# DebugCAN.net
KiCad netlist of a schematic drawn in EAGLE
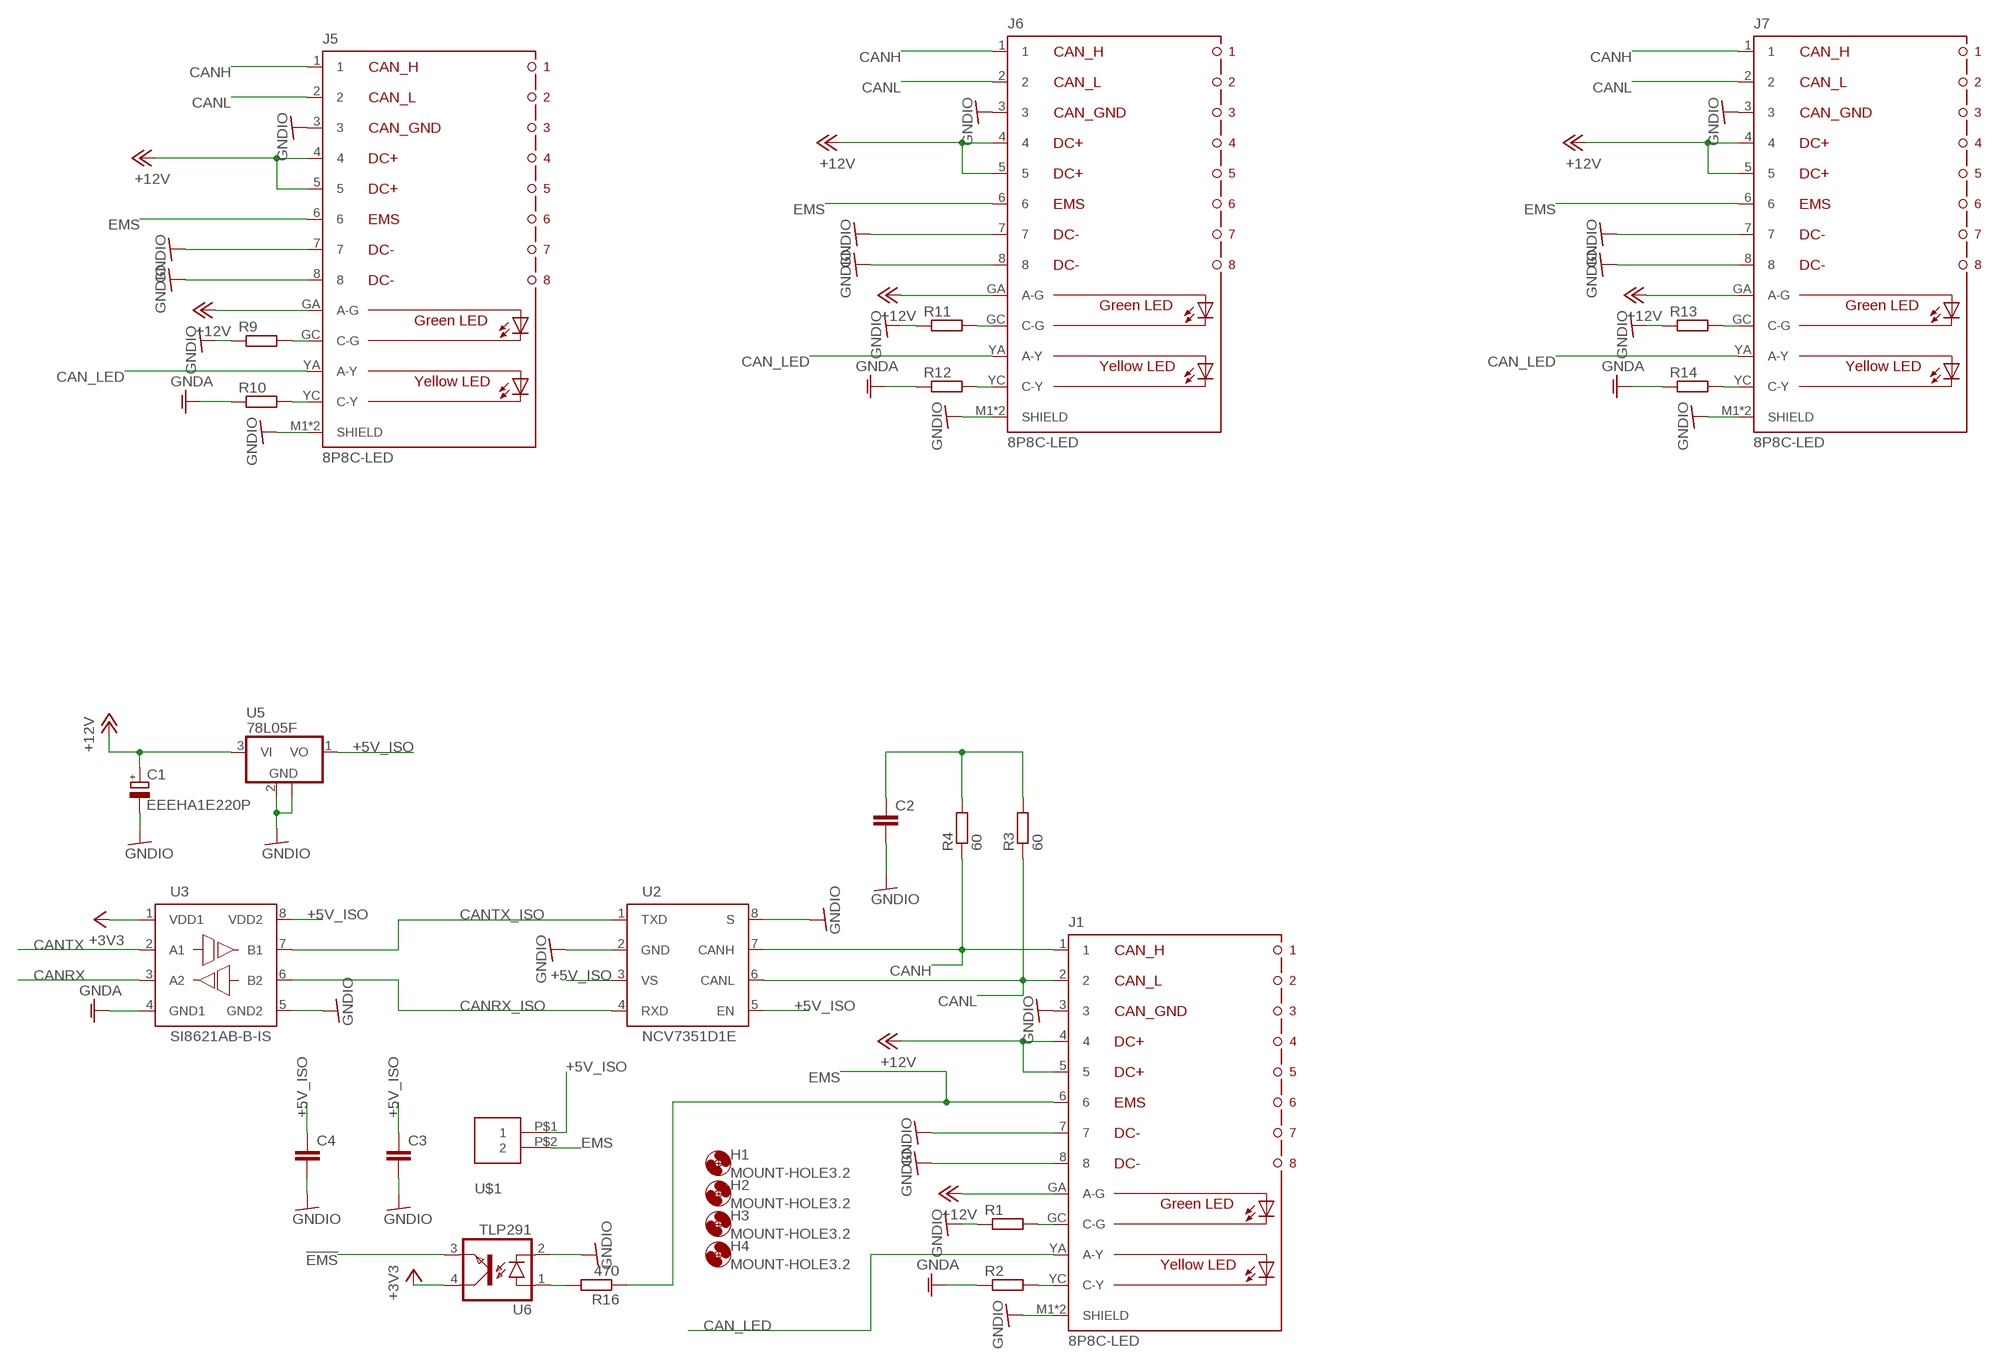
[diagram p0: schematic, sheet 1]
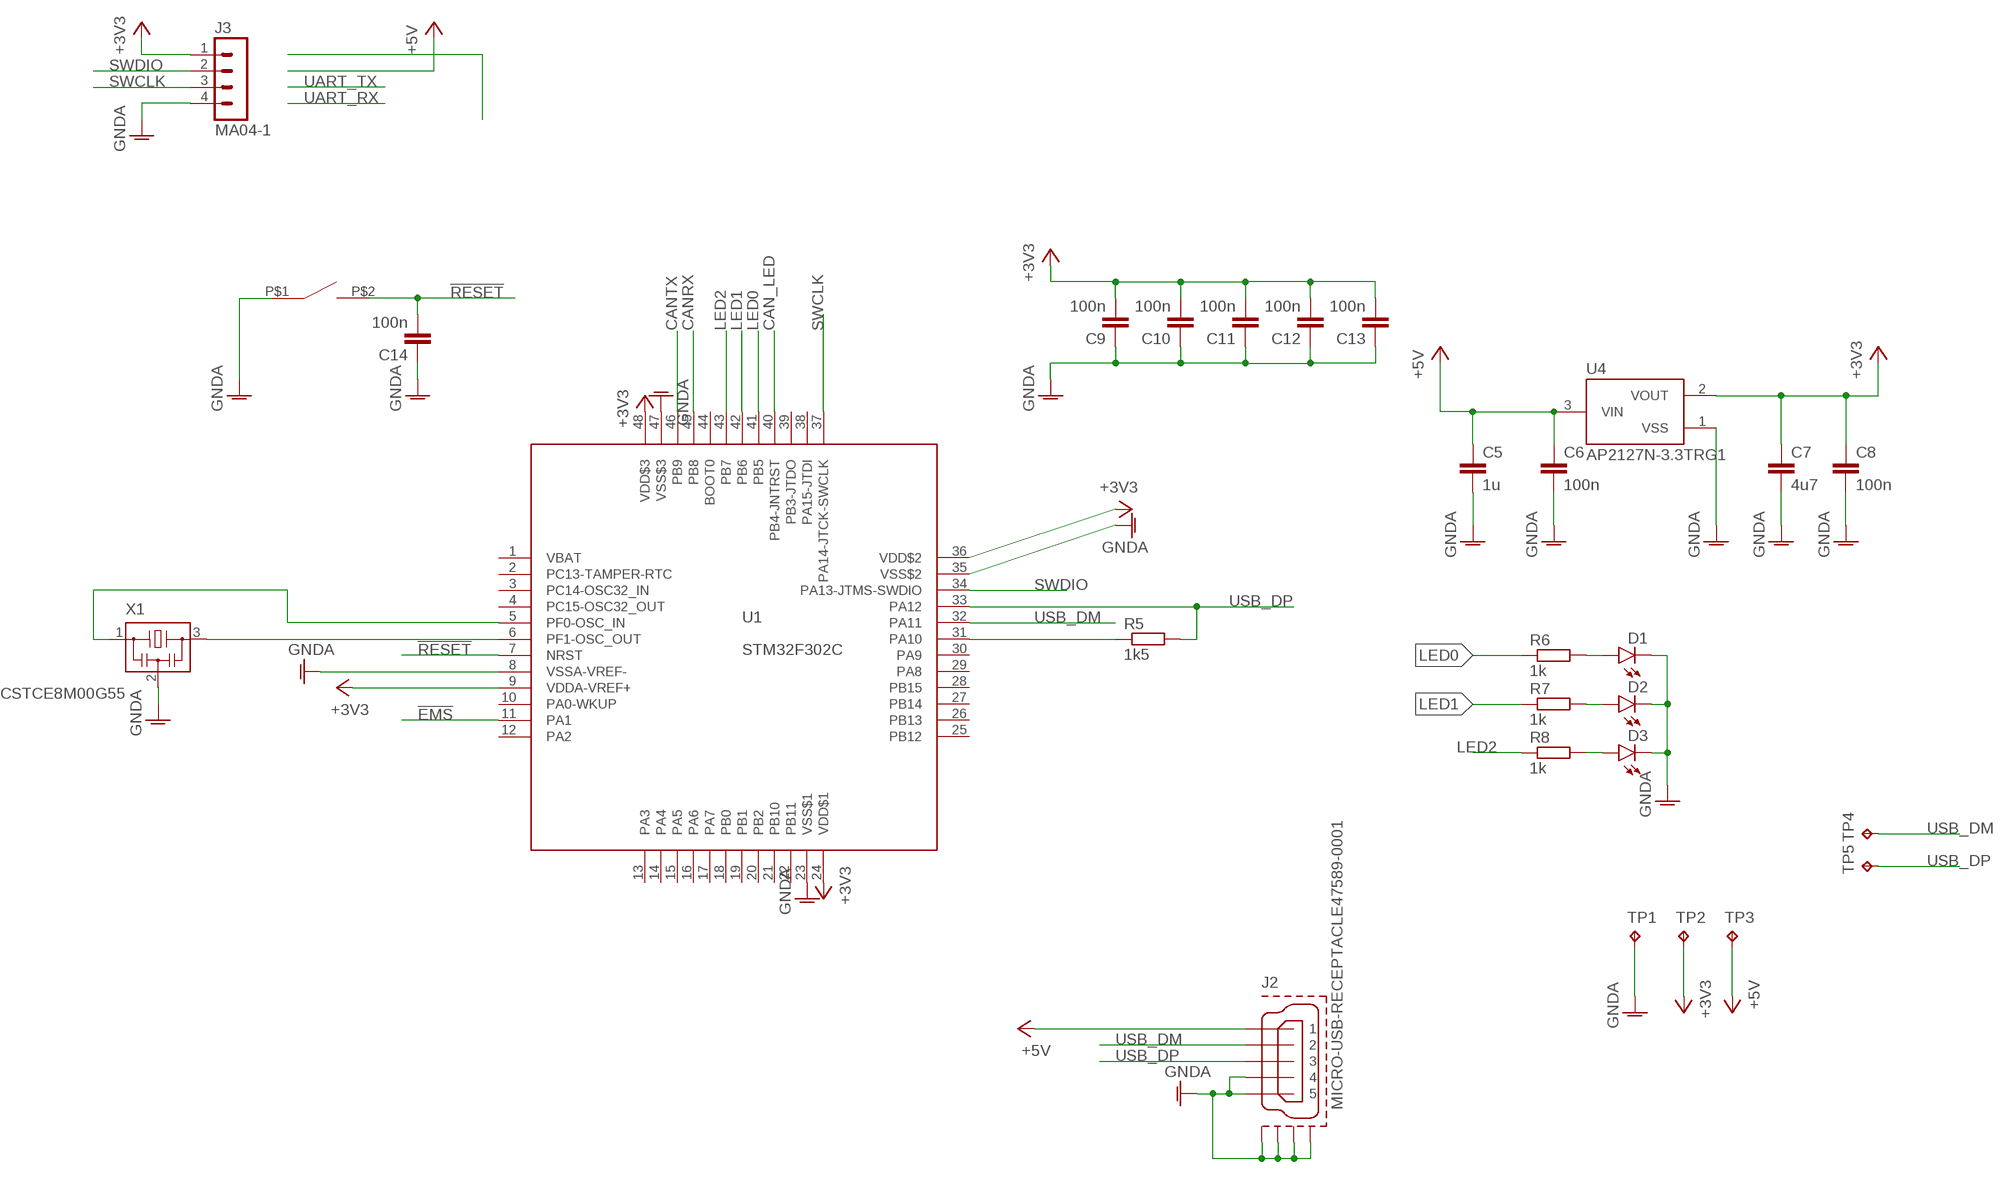
[diagram p1: schematic, sheet 2]

(export (version "E")
  (design (tool "Eeschema 10.0.6"))
  (components
    (comp (ref "C5")
      (value "1u")
      (footprint "eagle-import:C0603")
      (libsource (lib "eagle-import") (part "C-EUC0603"))
    )
    (comp (ref "C6")
      (value "100n")
      (footprint "eagle-import:C0603")
      (libsource (lib "eagle-import") (part "C-EUC0603"))
    )
    (comp (ref "C7")
      (value "4u7")
      (footprint "eagle-import:C0805")
      (libsource (lib "eagle-import") (part "C-EUC0805"))
    )
    (comp (ref "C8")
      (value "100n")
      (footprint "eagle-import:C0603")
      (libsource (lib "eagle-import") (part "C-EUC0603"))
    )
    (comp (ref "C9")
      (value "100n")
      (footprint "eagle-import:C0603")
      (libsource (lib "eagle-import") (part "C-EUC0603"))
    )
    (comp (ref "C10")
      (value "100n")
      (footprint "eagle-import:C0603")
      (libsource (lib "eagle-import") (part "C-EUC0603"))
    )
    (comp (ref "C11")
      (value "100n")
      (footprint "eagle-import:C0603")
      (libsource (lib "eagle-import") (part "C-EUC0603"))
    )
    (comp (ref "C12")
      (value "100n")
      (footprint "eagle-import:C0603")
      (libsource (lib "eagle-import") (part "C-EUC0603"))
    )
    (comp (ref "C13")
      (value "100n")
      (footprint "eagle-import:C0603")
      (libsource (lib "eagle-import") (part "C-EUC0603"))
    )
    (comp (ref "C14")
      (value "100n")
      (footprint "eagle-import:C0603")
      (libsource (lib "eagle-import") (part "C-EUC0603"))
    )
    (comp (ref "D1")
      (value "LEDCHIPLED_0805")
      (footprint "eagle-import:CHIPLED_0805")
      (libsource (lib "eagle-import") (part "LEDCHIPLED_0805"))
    )
    (comp (ref "D2")
      (value "LEDCHIPLED_0805")
      (footprint "eagle-import:CHIPLED_0805")
      (libsource (lib "eagle-import") (part "LEDCHIPLED_0805"))
    )
    (comp (ref "D3")
      (value "LEDCHIPLED_0805")
      (footprint "eagle-import:CHIPLED_0805")
      (libsource (lib "eagle-import") (part "LEDCHIPLED_0805"))
    )
    (comp (ref "J2")
      (value "MICRO-USB-RECEPTACLE47589-0001")
      (footprint "eagle-import:47589-0001")
      (libsource (lib "eagle-import") (part "MICRO-USB-RECEPTACLE47589-0001"))
    )
    (comp (ref "J3")
      (value "MA04-1")
      (footprint "eagle-import:MA04-1")
      (libsource (lib "eagle-import") (part "MA04-1"))
    )
    (comp (ref "R5")
      (value "1k5")
      (footprint "eagle-import:R0603")
      (libsource (lib "eagle-import") (part "R-EU_R0603"))
    )
    (comp (ref "R6")
      (value "1k")
      (footprint "eagle-import:R0603")
      (libsource (lib "eagle-import") (part "R-EU_R0603"))
    )
    (comp (ref "R7")
      (value "1k")
      (footprint "eagle-import:R0603")
      (libsource (lib "eagle-import") (part "R-EU_R0603"))
    )
    (comp (ref "R8")
      (value "1k")
      (footprint "eagle-import:R0603")
      (libsource (lib "eagle-import") (part "R-EU_R0603"))
    )
    (comp (ref "S1")
      (value "SWITCH_TACTILETOP")
      (footprint "eagle-import:SWITCH_TACTILE_3X6")
      (libsource (lib "eagle-import") (part "SWITCH_TACTILETOP"))
    )
    (comp (ref "TP1")
      (value "TPB1,27")
      (footprint "eagle-import:B1,27")
      (libsource (lib "eagle-import") (part "TPB1,27"))
    )
    (comp (ref "TP2")
      (value "TPB1,27")
      (footprint "eagle-import:B1,27")
      (libsource (lib "eagle-import") (part "TPB1,27"))
    )
    (comp (ref "TP3")
      (value "TPB1,27")
      (footprint "eagle-import:B1,27")
      (libsource (lib "eagle-import") (part "TPB1,27"))
    )
    (comp (ref "TP4")
      (value "TPB1,27")
      (footprint "eagle-import:B1,27")
      (libsource (lib "eagle-import") (part "TPB1,27"))
    )
    (comp (ref "TP5")
      (value "TPB1,27")
      (footprint "eagle-import:B1,27")
      (libsource (lib "eagle-import") (part "TPB1,27"))
    )
    (comp (ref "U1")
      (value "STM32F302C")
      (footprint "eagle-import:LQFP48")
      (libsource (lib "eagle-import") (part "STM32F303C"))
    )
    (comp (ref "U4")
      (value "AP2127N-3.3TRG1")
      (footprint "eagle-import:SOT95P240X110-3")
      (libsource (lib "eagle-import") (part "XC6206"))
    )
    (comp (ref "X1")
      (value "CSTCE8M00G55")
      (footprint "eagle-import:CSTCE8M00G55")
      (libsource (lib "eagle-import") (part "CSTCE8M00G55"))
    )
    (comp (ref "C1")
      (value "EEEHA1E220P")
      (footprint "eagle-import:153CLV-0605")
      (libsource (lib "eagle-import") (part "CPOL-EU153CLV-0605"))
    )
    (comp (ref "C2")
      (value "C-EUC0603")
      (footprint "eagle-import:C0603")
      (libsource (lib "eagle-import") (part "rcl_334_C-EUC0603"))
    )
    (comp (ref "C3")
      (value "C-EUC0603")
      (footprint "eagle-import:C0603")
      (libsource (lib "eagle-import") (part "rcl_334_C-EUC0603"))
    )
    (comp (ref "C4")
      (value "C-EUC0603")
      (footprint "eagle-import:C0603")
      (libsource (lib "eagle-import") (part "rcl_334_C-EUC0603"))
    )
    (comp (ref "H1")
      (value "MOUNT-HOLE3.2")
      (footprint "eagle-import:3,2")
      (libsource (lib "eagle-import") (part "MOUNT-HOLE3.2"))
    )
    (comp (ref "H2")
      (value "MOUNT-HOLE3.2")
      (footprint "eagle-import:3,2")
      (libsource (lib "eagle-import") (part "MOUNT-HOLE3.2"))
    )
    (comp (ref "H3")
      (value "MOUNT-HOLE3.2")
      (footprint "eagle-import:3,2")
      (libsource (lib "eagle-import") (part "MOUNT-HOLE3.2"))
    )
    (comp (ref "H4")
      (value "MOUNT-HOLE3.2")
      (footprint "eagle-import:3,2")
      (libsource (lib "eagle-import") (part "MOUNT-HOLE3.2"))
    )
    (comp (ref "J1")
      (value "8P8C-LED")
      (footprint "eagle-import:8P8C-LED")
      (libsource (lib "eagle-import") (part "8P8C-LED"))
    )
    (comp (ref "J5")
      (value "8P8C-LED")
      (footprint "eagle-import:8P8C-LED")
      (libsource (lib "eagle-import") (part "8P8C-LED"))
    )
    (comp (ref "J6")
      (value "8P8C-LED")
      (footprint "eagle-import:8P8C-LED")
      (libsource (lib "eagle-import") (part "8P8C-LED"))
    )
    (comp (ref "J7")
      (value "8P8C-LED")
      (footprint "eagle-import:8P8C-LED")
      (libsource (lib "eagle-import") (part "8P8C-LED"))
    )
    (comp (ref "R1")
      (value "R-EU_R0603")
      (footprint "eagle-import:R0603")
      (libsource (lib "eagle-import") (part "rcl_334_R-EU_R0603"))
    )
    (comp (ref "R2")
      (value "R-EU_R0603")
      (footprint "eagle-import:R0603")
      (libsource (lib "eagle-import") (part "rcl_334_R-EU_R0603"))
    )
    (comp (ref "R3")
      (value "60")
      (footprint "eagle-import:R0603")
      (libsource (lib "eagle-import") (part "rcl_334_R-EU_R0603"))
    )
    (comp (ref "R4")
      (value "60")
      (footprint "eagle-import:R0603")
      (libsource (lib "eagle-import") (part "rcl_334_R-EU_R0603"))
    )
    (comp (ref "R9")
      (value "R-EU_R0603")
      (footprint "eagle-import:R0603")
      (libsource (lib "eagle-import") (part "rcl_334_R-EU_R0603"))
    )
    (comp (ref "R10")
      (value "R-EU_R0603")
      (footprint "eagle-import:R0603")
      (libsource (lib "eagle-import") (part "rcl_334_R-EU_R0603"))
    )
    (comp (ref "R11")
      (value "R-EU_R0603")
      (footprint "eagle-import:R0603")
      (libsource (lib "eagle-import") (part "rcl_334_R-EU_R0603"))
    )
    (comp (ref "R12")
      (value "R-EU_R0603")
      (footprint "eagle-import:R0603")
      (libsource (lib "eagle-import") (part "rcl_334_R-EU_R0603"))
    )
    (comp (ref "R13")
      (value "R-EU_R0603")
      (footprint "eagle-import:R0603")
      (libsource (lib "eagle-import") (part "rcl_334_R-EU_R0603"))
    )
    (comp (ref "R14")
      (value "R-EU_R0603")
      (footprint "eagle-import:R0603")
      (libsource (lib "eagle-import") (part "rcl_334_R-EU_R0603"))
    )
    (comp (ref "R16")
      (value "470")
      (footprint "eagle-import:R0603")
      (libsource (lib "eagle-import") (part "rcl_334_R-EU_R0603"))
    )
    (comp (ref "U$1")
      (value "XH-2-STRAIGHT")
      (footprint "eagle-import:CON-XH-2-STRAIGHT")
      (libsource (lib "eagle-import") (part "XH-2-STRAIGHT"))
    )
    (comp (ref "U2")
      (value "NCV7351D1E")
      (footprint "eagle-import:SO08")
      (libsource (lib "eagle-import") (part "NCV7351D1E"))
    )
    (comp (ref "U3")
      (value "SI8621AB-B-IS")
      (footprint "eagle-import:SO08")
      (libsource (lib "eagle-import") (part "SI8621AB-B-IS"))
    )
    (comp (ref "U5")
      (value "78L05F")
      (footprint "eagle-import:SOT89")
      (libsource (lib "eagle-import") (part "78LF05"))
    )
    (comp (ref "U6")
      (value "TLP291")
      (footprint "eagle-import:MINI-FLAT-4")
      (libsource (lib "eagle-import") (part "TLP291"))
    )
  )
  (nets
    (net (code "1") (name "+3V3") (class "Default")
      (node (ref "C10") (pin "2") (pinfunction "2_2") (pintype "passive"))
      (node (ref "C11") (pin "2") (pinfunction "2_2") (pintype "passive"))
      (node (ref "C12") (pin "2") (pinfunction "2_2") (pintype "passive"))
      (node (ref "C13") (pin "2") (pinfunction "2_2") (pintype "passive"))
      (node (ref "C7") (pin "1") (pinfunction "1_1") (pintype "passive"))
      (node (ref "C8") (pin "1") (pinfunction "1_1") (pintype "passive"))
      (node (ref "C9") (pin "2") (pinfunction "2_2") (pintype "passive"))
      (node (ref "J3") (pin "1") (pinfunction "1_1") (pintype "passive"))
      (node (ref "TP2") (pin "TP") (pinfunction "TP_TP") (pintype "input"))
      (node (ref "U1") (pin "24") (pinfunction "VDD$1_24") (pintype "passive"))
      (node (ref "U1") (pin "36") (pinfunction "VDD$2_36") (pintype "passive"))
      (node (ref "U1") (pin "48") (pinfunction "VDD$3_48") (pintype "passive"))
      (node (ref "U1") (pin "9") (pinfunction "VDDA-VREF+_9") (pintype "bidirectional"))
      (node (ref "U3") (pin "1") (pinfunction "VDD1_1") (pintype "power_in"))
      (node (ref "U4") (pin "2") (pinfunction "VOUT_2") (pintype "bidirectional"))
      (node (ref "U6") (pin "4") (pinfunction "COL_4") (pintype "passive"))
    )
    (net (code "2") (name "+5V") (class "Default")
      (node (ref "C5") (pin "1") (pinfunction "1_1") (pintype "passive"))
      (node (ref "C6") (pin "1") (pinfunction "1_1") (pintype "passive"))
      (node (ref "J2") (pin "1") (pinfunction "1_1") (pintype "input"))
      (node (ref "TP3") (pin "TP") (pinfunction "TP_TP") (pintype "input"))
      (node (ref "U4") (pin "3") (pinfunction "VIN_3") (pintype "bidirectional"))
    )
    (net (code "3") (name "+5V_ISO") (class "Default")
      (node (ref "C3") (pin "1") (pinfunction "1_1") (pintype "passive"))
      (node (ref "C4") (pin "1") (pinfunction "1_1") (pintype "passive"))
      (node (ref "U$1") (pin "P$1") (pinfunction "1_P$1") (pintype "bidirectional"))
      (node (ref "U2") (pin "3") (pinfunction "VS_3") (pintype "power_in"))
      (node (ref "U2") (pin "5") (pinfunction "EN_5") (pintype "input"))
      (node (ref "U3") (pin "8") (pinfunction "VDD2_8") (pintype "power_in"))
      (node (ref "U5") (pin "1") (pinfunction "VO_1") (pintype "passive"))
    )
    (net (code "4") (name "+12V") (class "Default")
      (node (ref "C1") (pin "+") (pinfunction "+_+") (pintype "passive"))
      (node (ref "J1") (pin "4") (pinfunction "4_4") (pintype "input"))
      (node (ref "J1") (pin "5") (pinfunction "5_5") (pintype "input"))
      (node (ref "J1") (pin "GA") (pinfunction "A-G_GA") (pintype "passive"))
      (node (ref "J5") (pin "4") (pinfunction "4_4") (pintype "input"))
      (node (ref "J5") (pin "5") (pinfunction "5_5") (pintype "input"))
      (node (ref "J5") (pin "GA") (pinfunction "A-G_GA") (pintype "passive"))
      (node (ref "J6") (pin "4") (pinfunction "4_4") (pintype "input"))
      (node (ref "J6") (pin "5") (pinfunction "5_5") (pintype "input"))
      (node (ref "J6") (pin "GA") (pinfunction "A-G_GA") (pintype "passive"))
      (node (ref "J7") (pin "4") (pinfunction "4_4") (pintype "input"))
      (node (ref "J7") (pin "5") (pinfunction "5_5") (pintype "input"))
      (node (ref "J7") (pin "GA") (pinfunction "A-G_GA") (pintype "passive"))
      (node (ref "U5") (pin "3") (pinfunction "VI_3") (pintype "input"))
    )
    (net (code "5") (name "CANH") (class "Default")
      (node (ref "J1") (pin "1") (pinfunction "1_1") (pintype "input"))
      (node (ref "J5") (pin "1") (pinfunction "1_1") (pintype "input"))
      (node (ref "J6") (pin "1") (pinfunction "1_1") (pintype "input"))
      (node (ref "J7") (pin "1") (pinfunction "1_1") (pintype "input"))
      (node (ref "R4") (pin "1") (pinfunction "1_1") (pintype "passive"))
      (node (ref "U2") (pin "7") (pinfunction "CANH_7") (pintype "output"))
    )
    (net (code "6") (name "CANL") (class "Default")
      (node (ref "J1") (pin "2") (pinfunction "2_2") (pintype "input"))
      (node (ref "J5") (pin "2") (pinfunction "2_2") (pintype "input"))
      (node (ref "J6") (pin "2") (pinfunction "2_2") (pintype "input"))
      (node (ref "J7") (pin "2") (pinfunction "2_2") (pintype "input"))
      (node (ref "R3") (pin "1") (pinfunction "1_1") (pintype "passive"))
      (node (ref "U2") (pin "6") (pinfunction "CANL_6") (pintype "output"))
    )
    (net (code "7") (name "CANRX") (class "Default")
      (node (ref "U1") (pin "45") (pinfunction "PB8_45") (pintype "bidirectional"))
      (node (ref "U3") (pin "3") (pinfunction "A2_3") (pintype "output"))
    )
    (net (code "8") (name "CANRX_ISO") (class "Default")
      (node (ref "U2") (pin "4") (pinfunction "RXD_4") (pintype "output"))
      (node (ref "U3") (pin "6") (pinfunction "B2_6") (pintype "output"))
    )
    (net (code "9") (name "CANTX") (class "Default")
      (node (ref "U1") (pin "46") (pinfunction "PB9_46") (pintype "bidirectional"))
      (node (ref "U3") (pin "2") (pinfunction "A1_2") (pintype "input"))
    )
    (net (code "10") (name "CANTX_ISO") (class "Default")
      (node (ref "U2") (pin "1") (pinfunction "TXD_1") (pintype "input"))
      (node (ref "U3") (pin "7") (pinfunction "B1_7") (pintype "output"))
    )
    (net (code "11") (name "CAN_LED") (class "Default")
      (node (ref "J1") (pin "YA") (pinfunction "A-Y_YA") (pintype "passive"))
      (node (ref "J5") (pin "YA") (pinfunction "A-Y_YA") (pintype "passive"))
      (node (ref "J6") (pin "YA") (pinfunction "A-Y_YA") (pintype "passive"))
      (node (ref "J7") (pin "YA") (pinfunction "A-Y_YA") (pintype "passive"))
      (node (ref "U1") (pin "40") (pinfunction "PB4-JNTRST_40") (pintype "bidirectional"))
    )
    (net (code "12") (name "EMS") (class "Default")
      (node (ref "J1") (pin "6") (pinfunction "6_6") (pintype "input"))
      (node (ref "J5") (pin "6") (pinfunction "6_6") (pintype "input"))
      (node (ref "J6") (pin "6") (pinfunction "6_6") (pintype "input"))
      (node (ref "J7") (pin "6") (pinfunction "6_6") (pintype "input"))
      (node (ref "R16") (pin "1") (pinfunction "1_1") (pintype "passive"))
      (node (ref "U$1") (pin "P$2") (pinfunction "2_P$2") (pintype "bidirectional"))
    )
    (net (code "13") (name "GNDA") (class "Default")
      (node (ref "C10") (pin "1") (pinfunction "1_1") (pintype "passive"))
      (node (ref "C11") (pin "1") (pinfunction "1_1") (pintype "passive"))
      (node (ref "C12") (pin "1") (pinfunction "1_1") (pintype "passive"))
      (node (ref "C13") (pin "1") (pinfunction "1_1") (pintype "passive"))
      (node (ref "C14") (pin "1") (pinfunction "1_1") (pintype "passive"))
      (node (ref "C5") (pin "2") (pinfunction "2_2") (pintype "passive"))
      (node (ref "C6") (pin "2") (pinfunction "2_2") (pintype "passive"))
      (node (ref "C7") (pin "2") (pinfunction "2_2") (pintype "passive"))
      (node (ref "C8") (pin "2") (pinfunction "2_2") (pintype "passive"))
      (node (ref "C9") (pin "1") (pinfunction "1_1") (pintype "passive"))
      (node (ref "D1") (pin "C") (pinfunction "C_C") (pintype "passive"))
      (node (ref "D2") (pin "C") (pinfunction "C_C") (pintype "passive"))
      (node (ref "D3") (pin "C") (pinfunction "C_C") (pintype "passive"))
      (node (ref "J2") (pin "4") (pinfunction "4_4") (pintype "input"))
      (node (ref "J2") (pin "5") (pinfunction "5_5") (pintype "input"))
      (node (ref "J2") (pin "CASING1") (pinfunction "GND1_CASING1") (pintype "bidirectional"))
      (node (ref "J2") (pin "CASING2") (pinfunction "GND2_CASING2") (pintype "bidirectional"))
      (node (ref "J2") (pin "CASING3") (pinfunction "GND3_CASING3") (pintype "bidirectional"))
      (node (ref "J2") (pin "CASING4") (pinfunction "GND4_CASING4") (pintype "bidirectional"))
      (node (ref "J2") (pin "P$1") (pinfunction "GND1_P$1") (pintype "bidirectional"))
      (node (ref "J2") (pin "P$2") (pinfunction "GND1_P$2") (pintype "bidirectional"))
      (node (ref "J2") (pin "P$3") (pinfunction "GND2_P$3") (pintype "bidirectional"))
      (node (ref "J2") (pin "P$4") (pinfunction "GND2_P$4") (pintype "bidirectional"))
      (node (ref "J3") (pin "4") (pinfunction "4_4") (pintype "passive"))
      (node (ref "R10") (pin "1") (pinfunction "1_1") (pintype "passive"))
      (node (ref "R12") (pin "1") (pinfunction "1_1") (pintype "passive"))
      (node (ref "R14") (pin "1") (pinfunction "1_1") (pintype "passive"))
      (node (ref "R2") (pin "1") (pinfunction "1_1") (pintype "passive"))
      (node (ref "S1") (pin "P$1") (pinfunction "1_P$1") (pintype "bidirectional"))
      (node (ref "TP1") (pin "TP") (pinfunction "TP_TP") (pintype "input"))
      (node (ref "U1") (pin "23") (pinfunction "VSS$1_23") (pintype "passive"))
      (node (ref "U1") (pin "35") (pinfunction "VSS$2_35") (pintype "passive"))
      (node (ref "U1") (pin "47") (pinfunction "VSS$3_47") (pintype "passive"))
      (node (ref "U1") (pin "8") (pinfunction "VSSA-VREF-_8") (pintype "bidirectional"))
      (node (ref "U3") (pin "4") (pinfunction "GND1_4") (pintype "power_in"))
      (node (ref "U4") (pin "1") (pinfunction "VSS_1") (pintype "bidirectional"))
      (node (ref "X1") (pin "2") (pinfunction "2_2") (pintype "passive"))
    )
    (net (code "14") (name "GNDIO") (class "Default")
      (node (ref "C1") (pin "-") (pinfunction "-_-") (pintype "passive"))
      (node (ref "C2") (pin "2") (pinfunction "2_2") (pintype "passive"))
      (node (ref "C3") (pin "2") (pinfunction "2_2") (pintype "passive"))
      (node (ref "C4") (pin "2") (pinfunction "2_2") (pintype "passive"))
      (node (ref "J1") (pin "3") (pinfunction "3_3") (pintype "input"))
      (node (ref "J1") (pin "7") (pinfunction "7_7") (pintype "input"))
      (node (ref "J1") (pin "8") (pinfunction "8_8") (pintype "input"))
      (node (ref "J1") (pin "M1") (pinfunction "SHIELD_M1") (pintype "passive"))
      (node (ref "J1") (pin "M2") (pinfunction "SHIELD_M2") (pintype "passive"))
      (node (ref "J5") (pin "3") (pinfunction "3_3") (pintype "input"))
      (node (ref "J5") (pin "7") (pinfunction "7_7") (pintype "input"))
      (node (ref "J5") (pin "8") (pinfunction "8_8") (pintype "input"))
      (node (ref "J5") (pin "M1") (pinfunction "SHIELD_M1") (pintype "passive"))
      (node (ref "J5") (pin "M2") (pinfunction "SHIELD_M2") (pintype "passive"))
      (node (ref "J6") (pin "3") (pinfunction "3_3") (pintype "input"))
      (node (ref "J6") (pin "7") (pinfunction "7_7") (pintype "input"))
      (node (ref "J6") (pin "8") (pinfunction "8_8") (pintype "input"))
      (node (ref "J6") (pin "M1") (pinfunction "SHIELD_M1") (pintype "passive"))
      (node (ref "J6") (pin "M2") (pinfunction "SHIELD_M2") (pintype "passive"))
      (node (ref "J7") (pin "3") (pinfunction "3_3") (pintype "input"))
      (node (ref "J7") (pin "7") (pinfunction "7_7") (pintype "input"))
      (node (ref "J7") (pin "8") (pinfunction "8_8") (pintype "input"))
      (node (ref "J7") (pin "M1") (pinfunction "SHIELD_M1") (pintype "passive"))
      (node (ref "J7") (pin "M2") (pinfunction "SHIELD_M2") (pintype "passive"))
      (node (ref "R1") (pin "1") (pinfunction "1_1") (pintype "passive"))
      (node (ref "R11") (pin "1") (pinfunction "1_1") (pintype "passive"))
      (node (ref "R13") (pin "1") (pinfunction "1_1") (pintype "passive"))
      (node (ref "R9") (pin "1") (pinfunction "1_1") (pintype "passive"))
      (node (ref "U2") (pin "2") (pinfunction "GND_2") (pintype "power_in"))
      (node (ref "U2") (pin "8") (pinfunction "S_8") (pintype "input"))
      (node (ref "U3") (pin "5") (pinfunction "GND2_5") (pintype "power_in"))
      (node (ref "U5") (pin "2") (pinfunction "GND_2") (pintype "passive"))
      (node (ref "U5") (pin "2@1") (pinfunction "GND_2@1") (pintype "passive"))
      (node (ref "U6") (pin "2") (pinfunction "C_2") (pintype "passive"))
    )
    (net (code "15") (name "LED0") (class "Default")
      (node (ref "R6") (pin "1") (pinfunction "1_1") (pintype "passive"))
      (node (ref "U1") (pin "41") (pinfunction "PB5_41") (pintype "bidirectional"))
    )
    (net (code "16") (name "LED1") (class "Default")
      (node (ref "R7") (pin "1") (pinfunction "1_1") (pintype "passive"))
      (node (ref "U1") (pin "42") (pinfunction "PB6_42") (pintype "bidirectional"))
    )
    (net (code "17") (name "LED2") (class "Default")
      (node (ref "R8") (pin "1") (pinfunction "1_1") (pintype "passive"))
      (node (ref "U1") (pin "43") (pinfunction "PB7_43") (pintype "bidirectional"))
    )
    (net (code "18") (name "Net-(C2-Pad1)") (class "Default")
      (node (ref "C2") (pin "1") (pinfunction "1_1") (pintype "passive"))
      (node (ref "R3") (pin "2") (pinfunction "2_2") (pintype "passive"))
      (node (ref "R4") (pin "2") (pinfunction "2_2") (pintype "passive"))
    )
    (net (code "19") (name "Net-(D1-PadA)") (class "Default")
      (node (ref "D1") (pin "A") (pinfunction "A_A") (pintype "passive"))
      (node (ref "R6") (pin "2") (pinfunction "2_2") (pintype "passive"))
    )
    (net (code "20") (name "Net-(D2-PadA)") (class "Default")
      (node (ref "D2") (pin "A") (pinfunction "A_A") (pintype "passive"))
      (node (ref "R7") (pin "2") (pinfunction "2_2") (pintype "passive"))
    )
    (net (code "21") (name "Net-(D3-PadA)") (class "Default")
      (node (ref "D3") (pin "A") (pinfunction "A_A") (pintype "passive"))
      (node (ref "R8") (pin "2") (pinfunction "2_2") (pintype "passive"))
    )
    (net (code "22") (name "Net-(J1-C-G)") (class "Default")
      (node (ref "J1") (pin "GC") (pinfunction "C-G_GC") (pintype "passive"))
      (node (ref "R1") (pin "2") (pinfunction "2_2") (pintype "passive"))
    )
    (net (code "23") (name "Net-(J1-C-Y)") (class "Default")
      (node (ref "J1") (pin "YC") (pinfunction "C-Y_YC") (pintype "passive"))
      (node (ref "R2") (pin "2") (pinfunction "2_2") (pintype "passive"))
    )
    (net (code "24") (name "Net-(J5-C-G)") (class "Default")
      (node (ref "J5") (pin "GC") (pinfunction "C-G_GC") (pintype "passive"))
      (node (ref "R9") (pin "2") (pinfunction "2_2") (pintype "passive"))
    )
    (net (code "25") (name "Net-(J5-C-Y)") (class "Default")
      (node (ref "J5") (pin "YC") (pinfunction "C-Y_YC") (pintype "passive"))
      (node (ref "R10") (pin "2") (pinfunction "2_2") (pintype "passive"))
    )
    (net (code "26") (name "Net-(J6-C-G)") (class "Default")
      (node (ref "J6") (pin "GC") (pinfunction "C-G_GC") (pintype "passive"))
      (node (ref "R11") (pin "2") (pinfunction "2_2") (pintype "passive"))
    )
    (net (code "27") (name "Net-(J6-C-Y)") (class "Default")
      (node (ref "J6") (pin "YC") (pinfunction "C-Y_YC") (pintype "passive"))
      (node (ref "R12") (pin "2") (pinfunction "2_2") (pintype "passive"))
    )
    (net (code "28") (name "Net-(J7-C-G)") (class "Default")
      (node (ref "J7") (pin "GC") (pinfunction "C-G_GC") (pintype "passive"))
      (node (ref "R13") (pin "2") (pinfunction "2_2") (pintype "passive"))
    )
    (net (code "29") (name "Net-(J7-C-Y)") (class "Default")
      (node (ref "J7") (pin "YC") (pinfunction "C-Y_YC") (pintype "passive"))
      (node (ref "R14") (pin "2") (pinfunction "2_2") (pintype "passive"))
    )
    (net (code "30") (name "Net-(U1-PA10)") (class "Default")
      (node (ref "R5") (pin "1") (pinfunction "1_1") (pintype "passive"))
      (node (ref "U1") (pin "31") (pinfunction "PA10_31") (pintype "bidirectional"))
    )
    (net (code "31") (name "Net-(U1-PF0-OSC_IN)") (class "Default")
      (node (ref "U1") (pin "5") (pinfunction "PF0-OSC_IN_5") (pintype "input"))
      (node (ref "X1") (pin "1") (pinfunction "1_1") (pintype "passive"))
    )
    (net (code "32") (name "Net-(U1-PF1-OSC_OUT)") (class "Default")
      (node (ref "U1") (pin "6") (pinfunction "PF1-OSC_OUT_6") (pintype "output"))
      (node (ref "X1") (pin "3") (pinfunction "3_3") (pintype "passive"))
    )
    (net (code "33") (name "Net-(U6-A)") (class "Default")
      (node (ref "R16") (pin "2") (pinfunction "2_2") (pintype "passive"))
      (node (ref "U6") (pin "1") (pinfunction "A_1") (pintype "passive"))
    )
    (net (code "34") (name "SWCLK") (class "Default")
      (node (ref "J3") (pin "3") (pinfunction "3_3") (pintype "passive"))
      (node (ref "U1") (pin "37") (pinfunction "PA14-JTCK-SWCLK_37") (pintype "bidirectional"))
    )
    (net (code "35") (name "SWDIO") (class "Default")
      (node (ref "J3") (pin "2") (pinfunction "2_2") (pintype "passive"))
      (node (ref "U1") (pin "34") (pinfunction "PA13-JTMS-SWDIO_34") (pintype "bidirectional"))
    )
    (net (code "38") (name "USB_DM") (class "Default")
      (node (ref "J2") (pin "2") (pinfunction "2_2") (pintype "input"))
      (node (ref "TP4") (pin "TP") (pinfunction "TP_TP") (pintype "input"))
      (node (ref "U1") (pin "32") (pinfunction "PA11_32") (pintype "bidirectional"))
    )
    (net (code "39") (name "USB_DP") (class "Default")
      (node (ref "J2") (pin "3") (pinfunction "3_3") (pintype "input"))
      (node (ref "R5") (pin "2") (pinfunction "2_2") (pintype "passive"))
      (node (ref "TP5") (pin "TP") (pinfunction "TP_TP") (pintype "input"))
      (node (ref "U1") (pin "33") (pinfunction "PA12_33") (pintype "bidirectional"))
    )
    (net (code "40") (name "unconnected-(U1-BOOT0-Pad44)") (class "Default")
      (node (ref "U1") (pin "44") (pinfunction "BOOT0_44") (pintype "input"))
    )
    (net (code "41") (name "unconnected-(U1-PA0-WKUP-Pad10)") (class "Default")
      (node (ref "U1") (pin "10") (pinfunction "PA0-WKUP_10") (pintype "bidirectional"))
    )
    (net (code "42") (name "unconnected-(U1-PA2-Pad12)") (class "Default")
      (node (ref "U1") (pin "12") (pinfunction "PA2_12") (pintype "bidirectional"))
    )
    (net (code "43") (name "unconnected-(U1-PA3-Pad13)") (class "Default")
      (node (ref "U1") (pin "13") (pinfunction "PA3_13") (pintype "bidirectional"))
    )
    (net (code "44") (name "unconnected-(U1-PA4-Pad14)") (class "Default")
      (node (ref "U1") (pin "14") (pinfunction "PA4_14") (pintype "bidirectional"))
    )
    (net (code "45") (name "unconnected-(U1-PA5-Pad15)") (class "Default")
      (node (ref "U1") (pin "15") (pinfunction "PA5_15") (pintype "bidirectional"))
    )
    (net (code "46") (name "unconnected-(U1-PA6-Pad16)") (class "Default")
      (node (ref "U1") (pin "16") (pinfunction "PA6_16") (pintype "bidirectional"))
    )
    (net (code "47") (name "unconnected-(U1-PA7-Pad17)") (class "Default")
      (node (ref "U1") (pin "17") (pinfunction "PA7_17") (pintype "bidirectional"))
    )
    (net (code "48") (name "unconnected-(U1-PA8-Pad29)") (class "Default")
      (node (ref "U1") (pin "29") (pinfunction "PA8_29") (pintype "bidirectional"))
    )
    (net (code "49") (name "unconnected-(U1-PA9-Pad30)") (class "Default")
      (node (ref "U1") (pin "30") (pinfunction "PA9_30") (pintype "bidirectional"))
    )
    (net (code "50") (name "unconnected-(U1-PA15-JTDI-Pad38)") (class "Default")
      (node (ref "U1") (pin "38") (pinfunction "PA15-JTDI_38") (pintype "bidirectional"))
    )
    (net (code "51") (name "unconnected-(U1-PB0-Pad18)") (class "Default")
      (node (ref "U1") (pin "18") (pinfunction "PB0_18") (pintype "bidirectional"))
    )
    (net (code "52") (name "unconnected-(U1-PB1-Pad19)") (class "Default")
      (node (ref "U1") (pin "19") (pinfunction "PB1_19") (pintype "bidirectional"))
    )
    (net (code "53") (name "unconnected-(U1-PB2-Pad20)") (class "Default")
      (node (ref "U1") (pin "20") (pinfunction "PB2_20") (pintype "bidirectional"))
    )
    (net (code "54") (name "unconnected-(U1-PB3-JTDO-Pad39)") (class "Default")
      (node (ref "U1") (pin "39") (pinfunction "PB3-JTDO_39") (pintype "bidirectional"))
    )
    (net (code "55") (name "unconnected-(U1-PB10-Pad21)") (class "Default")
      (node (ref "U1") (pin "21") (pinfunction "PB10_21") (pintype "bidirectional"))
    )
    (net (code "56") (name "unconnected-(U1-PB11-Pad22)") (class "Default")
      (node (ref "U1") (pin "22") (pinfunction "PB11_22") (pintype "bidirectional"))
    )
    (net (code "57") (name "unconnected-(U1-PB12-Pad25)") (class "Default")
      (node (ref "U1") (pin "25") (pinfunction "PB12_25") (pintype "bidirectional"))
    )
    (net (code "58") (name "unconnected-(U1-PB13-Pad26)") (class "Default")
      (node (ref "U1") (pin "26") (pinfunction "PB13_26") (pintype "bidirectional"))
    )
    (net (code "59") (name "unconnected-(U1-PB14-Pad27)") (class "Default")
      (node (ref "U1") (pin "27") (pinfunction "PB14_27") (pintype "bidirectional"))
    )
    (net (code "60") (name "unconnected-(U1-PB15-Pad28)") (class "Default")
      (node (ref "U1") (pin "28") (pinfunction "PB15_28") (pintype "bidirectional"))
    )
    (net (code "61") (name "unconnected-(U1-PC13-TAMPER-RTC-Pad2)") (class "Default")
      (node (ref "U1") (pin "2") (pinfunction "PC13-TAMPER-RTC_2") (pintype "bidirectional"))
    )
    (net (code "62") (name "unconnected-(U1-PC14-OSC32_IN-Pad3)") (class "Default")
      (node (ref "U1") (pin "3") (pinfunction "PC14-OSC32_IN_3") (pintype "bidirectional"))
    )
    (net (code "63") (name "unconnected-(U1-PC15-OSC32_OUT-Pad4)") (class "Default")
      (node (ref "U1") (pin "4") (pinfunction "PC15-OSC32_OUT_4") (pintype "bidirectional"))
    )
    (net (code "64") (name "unconnected-(U1-VBAT-Pad1)") (class "Default")
      (node (ref "U1") (pin "1") (pinfunction "VBAT_1") (pintype "passive"))
    )
    (net (code "65") (name "~{EMS}") (class "Default")
      (node (ref "U1") (pin "11") (pinfunction "PA1_11") (pintype "bidirectional"))
      (node (ref "U6") (pin "3") (pinfunction "EMIT_3") (pintype "passive"))
    )
    (net (code "66") (name "~{RESET}") (class "Default")
      (node (ref "C14") (pin "2") (pinfunction "2_2") (pintype "passive"))
      (node (ref "S1") (pin "P$2") (pinfunction "2_P$2") (pintype "bidirectional"))
      (node (ref "U1") (pin "7") (pinfunction "NRST_7") (pintype "bidirectional"))
    )
  )
)
